# dms_sensor_board.net
KiCad netlist of a schematic drawn in EAGLE
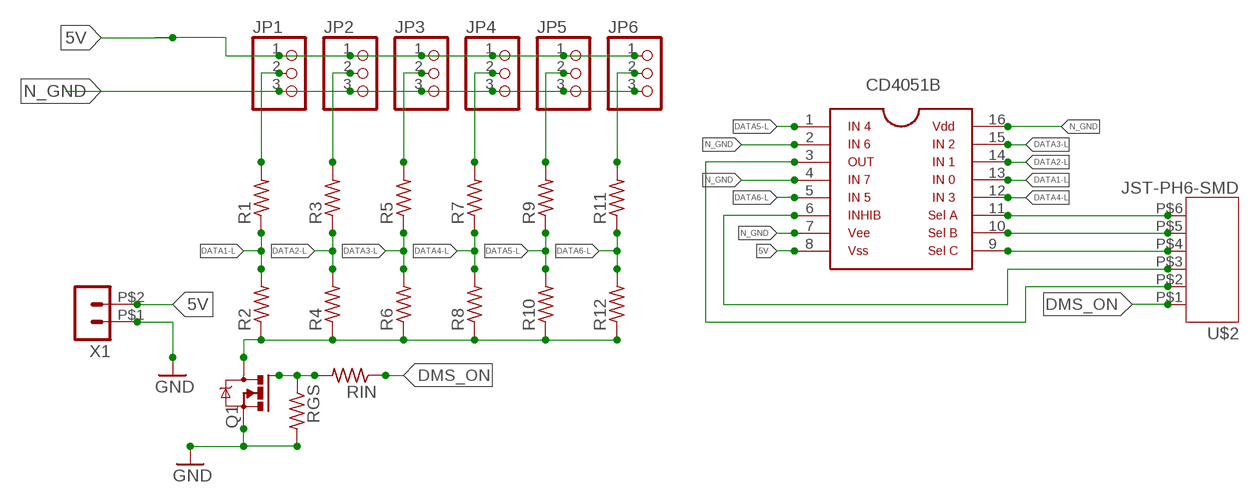
[diagram p0: schematic, sheet 1]

(export (version "E")
  (design (tool "Eeschema 10.0.6"))
  (components
    (comp (ref "JP1")
      (value "PINHD-1X03_2.00")
      (footprint "eagle-import:1X03M")
      (libsource (lib "eagle-import") (part "PINHD-1X03_2.00"))
    )
    (comp (ref "JP2")
      (value "PINHD-1X03_2.00")
      (footprint "eagle-import:1X03M")
      (libsource (lib "eagle-import") (part "PINHD-1X03_2.00"))
    )
    (comp (ref "JP3")
      (value "PINHD-1X03_2.00")
      (footprint "eagle-import:1X03M")
      (libsource (lib "eagle-import") (part "PINHD-1X03_2.00"))
    )
    (comp (ref "JP4")
      (value "PINHD-1X03_2.00")
      (footprint "eagle-import:1X03M")
      (libsource (lib "eagle-import") (part "PINHD-1X03_2.00"))
    )
    (comp (ref "JP5")
      (value "PINHD-1X03_2.00")
      (footprint "eagle-import:1X03M")
      (libsource (lib "eagle-import") (part "PINHD-1X03_2.00"))
    )
    (comp (ref "JP6")
      (value "PINHD-1X03_2.00")
      (footprint "eagle-import:1X03M")
      (libsource (lib "eagle-import") (part "PINHD-1X03_2.00"))
    )
    (comp (ref "MUX1")
      (value "8X1")
      (footprint "eagle-import:SO16")
      (libsource (lib "eagle-import") (part "8X1_ANALOG_MUX"))
    )
    (comp (ref "Q1")
      (value "IRLML5203")
      (footprint "eagle-import:MICRO3")
      (libsource (lib "eagle-import") (part "IRLML5203"))
    )
    (comp (ref "R1")
      (value "R-US_R0805")
      (footprint "eagle-import:R0805")
      (libsource (lib "eagle-import") (part "R-US_R0805"))
    )
    (comp (ref "R2")
      (value "R-US_R0805")
      (footprint "eagle-import:R0805")
      (libsource (lib "eagle-import") (part "R-US_R0805"))
    )
    (comp (ref "R3")
      (value "R-US_R0805")
      (footprint "eagle-import:R0805")
      (libsource (lib "eagle-import") (part "R-US_R0805"))
    )
    (comp (ref "R4")
      (value "R-US_R0805")
      (footprint "eagle-import:R0805")
      (libsource (lib "eagle-import") (part "R-US_R0805"))
    )
    (comp (ref "R5")
      (value "R-US_R0805")
      (footprint "eagle-import:R0805")
      (libsource (lib "eagle-import") (part "R-US_R0805"))
    )
    (comp (ref "R6")
      (value "R-US_R0805")
      (footprint "eagle-import:R0805")
      (libsource (lib "eagle-import") (part "R-US_R0805"))
    )
    (comp (ref "R7")
      (value "R-US_R0805")
      (footprint "eagle-import:R0805")
      (libsource (lib "eagle-import") (part "R-US_R0805"))
    )
    (comp (ref "R8")
      (value "R-US_R0805")
      (footprint "eagle-import:R0805")
      (libsource (lib "eagle-import") (part "R-US_R0805"))
    )
    (comp (ref "R9")
      (value "R-US_R0805")
      (footprint "eagle-import:R0805")
      (libsource (lib "eagle-import") (part "R-US_R0805"))
    )
    (comp (ref "R10")
      (value "R-US_R0805")
      (footprint "eagle-import:R0805")
      (libsource (lib "eagle-import") (part "R-US_R0805"))
    )
    (comp (ref "R11")
      (value "R-US_R0805")
      (footprint "eagle-import:R0805")
      (libsource (lib "eagle-import") (part "R-US_R0805"))
    )
    (comp (ref "R12")
      (value "R-US_R0805")
      (footprint "eagle-import:R0805")
      (libsource (lib "eagle-import") (part "R-US_R0805"))
    )
    (comp (ref "RGS")
      (value "R-US_R0805")
      (footprint "eagle-import:R0805")
      (libsource (lib "eagle-import") (part "R-US_R0805"))
    )
    (comp (ref "RIN")
      (value "R-US_R0805")
      (footprint "eagle-import:R0805")
      (libsource (lib "eagle-import") (part "R-US_R0805"))
    )
    (comp (ref "U$2")
      (value "JST-PH6-SMD")
      (footprint "eagle-import:JST-PH6-SMD")
      (libsource (lib "eagle-import") (part "JST-PH6-SMD"))
    )
    (comp (ref "X1")
      (value "HEADER_POS2_43045-0206")
      (footprint "eagle-import:43045-0206")
      (libsource (lib "eagle-import") (part "HEADER_POS2_?43045-0206"))
    )
  )
  (nets
    (net (code "1") (name "5V") (class "Default")
      (node (ref "JP1") (pin "1") (pinfunction "1_1") (pintype "passive"))
      (node (ref "JP2") (pin "1") (pinfunction "1_1") (pintype "passive"))
      (node (ref "JP3") (pin "1") (pinfunction "1_1") (pintype "passive"))
      (node (ref "JP4") (pin "1") (pinfunction "1_1") (pintype "passive"))
      (node (ref "JP5") (pin "1") (pinfunction "1_1") (pintype "passive"))
      (node (ref "JP6") (pin "1") (pinfunction "1_1") (pintype "passive"))
      (node (ref "MUX1") (pin "8") (pinfunction "P$8_8") (pintype "bidirectional"))
      (node (ref "X1") (pin "P$2") (pinfunction "2_P$2") (pintype "passive"))
    )
    (net (code "2") (name "DATA1-L") (class "Default")
      (node (ref "MUX1") (pin "13") (pinfunction "P$13_13") (pintype "bidirectional"))
      (node (ref "R1") (pin "1") (pinfunction "1_1") (pintype "passive"))
      (node (ref "R2") (pin "2") (pinfunction "2_2") (pintype "passive"))
    )
    (net (code "3") (name "DATA2-L") (class "Default")
      (node (ref "MUX1") (pin "14") (pinfunction "P$14_14") (pintype "bidirectional"))
      (node (ref "R3") (pin "1") (pinfunction "1_1") (pintype "passive"))
      (node (ref "R4") (pin "2") (pinfunction "2_2") (pintype "passive"))
    )
    (net (code "4") (name "DATA3-L") (class "Default")
      (node (ref "MUX1") (pin "15") (pinfunction "P$15_15") (pintype "bidirectional"))
      (node (ref "R5") (pin "1") (pinfunction "1_1") (pintype "passive"))
      (node (ref "R6") (pin "2") (pinfunction "2_2") (pintype "passive"))
    )
    (net (code "5") (name "DATA4-L") (class "Default")
      (node (ref "MUX1") (pin "12") (pinfunction "P$12_12") (pintype "bidirectional"))
      (node (ref "R7") (pin "1") (pinfunction "1_1") (pintype "passive"))
      (node (ref "R8") (pin "2") (pinfunction "2_2") (pintype "passive"))
    )
    (net (code "6") (name "DATA5-L") (class "Default")
      (node (ref "MUX1") (pin "1") (pinfunction "P$1_1") (pintype "bidirectional"))
      (node (ref "R10") (pin "2") (pinfunction "2_2") (pintype "passive"))
      (node (ref "R9") (pin "1") (pinfunction "1_1") (pintype "passive"))
    )
    (net (code "7") (name "DATA6-L") (class "Default")
      (node (ref "MUX1") (pin "5") (pinfunction "P$5_5") (pintype "bidirectional"))
      (node (ref "R11") (pin "1") (pinfunction "1_1") (pintype "passive"))
      (node (ref "R12") (pin "2") (pinfunction "2_2") (pintype "passive"))
    )
    (net (code "8") (name "DMS_ON") (class "Default")
      (node (ref "RIN") (pin "1") (pinfunction "1_1") (pintype "passive"))
      (node (ref "U$2") (pin "P$1") (pinfunction "1_P$1") (pintype "passive"))
    )
    (net (code "9") (name "GND") (class "Default")
      (node (ref "Q1") (pin "3") (pinfunction "S_3") (pintype "passive"))
      (node (ref "RGS") (pin "2") (pinfunction "2_2") (pintype "passive"))
      (node (ref "X1") (pin "P$1") (pinfunction "1_P$1") (pintype "passive"))
    )
    (net (code "10") (name "N_GND") (class "Default")
      (node (ref "JP1") (pin "3") (pinfunction "3_3") (pintype "passive"))
      (node (ref "JP2") (pin "3") (pinfunction "3_3") (pintype "passive"))
      (node (ref "JP3") (pin "3") (pinfunction "3_3") (pintype "passive"))
      (node (ref "JP4") (pin "3") (pinfunction "3_3") (pintype "passive"))
      (node (ref "JP5") (pin "3") (pinfunction "3_3") (pintype "passive"))
      (node (ref "JP6") (pin "3") (pinfunction "3_3") (pintype "passive"))
      (node (ref "MUX1") (pin "16") (pinfunction "P$16_16") (pintype "bidirectional"))
      (node (ref "MUX1") (pin "2") (pinfunction "P$2_2") (pintype "bidirectional"))
      (node (ref "MUX1") (pin "4") (pinfunction "P$4_4") (pintype "bidirectional"))
      (node (ref "MUX1") (pin "7") (pinfunction "P$7_7") (pintype "bidirectional"))
      (node (ref "Q1") (pin "2") (pinfunction "D_2") (pintype "passive"))
      (node (ref "R10") (pin "1") (pinfunction "1_1") (pintype "passive"))
      (node (ref "R12") (pin "1") (pinfunction "1_1") (pintype "passive"))
      (node (ref "R2") (pin "1") (pinfunction "1_1") (pintype "passive"))
      (node (ref "R4") (pin "1") (pinfunction "1_1") (pintype "passive"))
      (node (ref "R6") (pin "1") (pinfunction "1_1") (pintype "passive"))
      (node (ref "R8") (pin "1") (pinfunction "1_1") (pintype "passive"))
    )
    (net (code "11") (name "Net-(JP1-Pad2)") (class "Default")
      (node (ref "JP1") (pin "2") (pinfunction "2_2") (pintype "passive"))
      (node (ref "R1") (pin "2") (pinfunction "2_2") (pintype "passive"))
    )
    (net (code "12") (name "Net-(JP2-Pad2)") (class "Default")
      (node (ref "JP2") (pin "2") (pinfunction "2_2") (pintype "passive"))
      (node (ref "R3") (pin "2") (pinfunction "2_2") (pintype "passive"))
    )
    (net (code "13") (name "Net-(JP3-Pad2)") (class "Default")
      (node (ref "JP3") (pin "2") (pinfunction "2_2") (pintype "passive"))
      (node (ref "R5") (pin "2") (pinfunction "2_2") (pintype "passive"))
    )
    (net (code "14") (name "Net-(JP4-Pad2)") (class "Default")
      (node (ref "JP4") (pin "2") (pinfunction "2_2") (pintype "passive"))
      (node (ref "R7") (pin "2") (pinfunction "2_2") (pintype "passive"))
    )
    (net (code "15") (name "Net-(JP5-Pad2)") (class "Default")
      (node (ref "JP5") (pin "2") (pinfunction "2_2") (pintype "passive"))
      (node (ref "R9") (pin "2") (pinfunction "2_2") (pintype "passive"))
    )
    (net (code "16") (name "Net-(JP6-Pad2)") (class "Default")
      (node (ref "JP6") (pin "2") (pinfunction "2_2") (pintype "passive"))
      (node (ref "R11") (pin "2") (pinfunction "2_2") (pintype "passive"))
    )
    (net (code "17") (name "Net-(MUX1-P$3)") (class "Default")
      (node (ref "MUX1") (pin "3") (pinfunction "P$3_3") (pintype "bidirectional"))
      (node (ref "U$2") (pin "P$2") (pinfunction "2_P$2") (pintype "passive"))
    )
    (net (code "18") (name "Net-(MUX1-P$6)") (class "Default")
      (node (ref "MUX1") (pin "6") (pinfunction "P$6_6") (pintype "bidirectional"))
      (node (ref "U$2") (pin "P$3") (pinfunction "3_P$3") (pintype "passive"))
    )
    (net (code "19") (name "Net-(MUX1-P$9)") (class "Default")
      (node (ref "MUX1") (pin "9") (pinfunction "P$9_9") (pintype "bidirectional"))
      (node (ref "U$2") (pin "P$4") (pinfunction "4_P$4") (pintype "passive"))
    )
    (net (code "20") (name "Net-(MUX1-P$10)") (class "Default")
      (node (ref "MUX1") (pin "10") (pinfunction "P$10_10") (pintype "bidirectional"))
      (node (ref "U$2") (pin "P$5") (pinfunction "5_P$5") (pintype "passive"))
    )
    (net (code "21") (name "Net-(MUX1-P$11)") (class "Default")
      (node (ref "MUX1") (pin "11") (pinfunction "P$11_11") (pintype "bidirectional"))
      (node (ref "U$2") (pin "P$6") (pinfunction "6_P$6") (pintype "passive"))
    )
    (net (code "22") (name "Net-(Q1-G)") (class "Default")
      (node (ref "Q1") (pin "1") (pinfunction "G_1") (pintype "passive"))
      (node (ref "RGS") (pin "1") (pinfunction "1_1") (pintype "passive"))
      (node (ref "RIN") (pin "2") (pinfunction "2_2") (pintype "passive"))
    )
  )
)
